# Control_board_POD_CMS.net
KiCad netlist of a schematic drawn in EAGLE
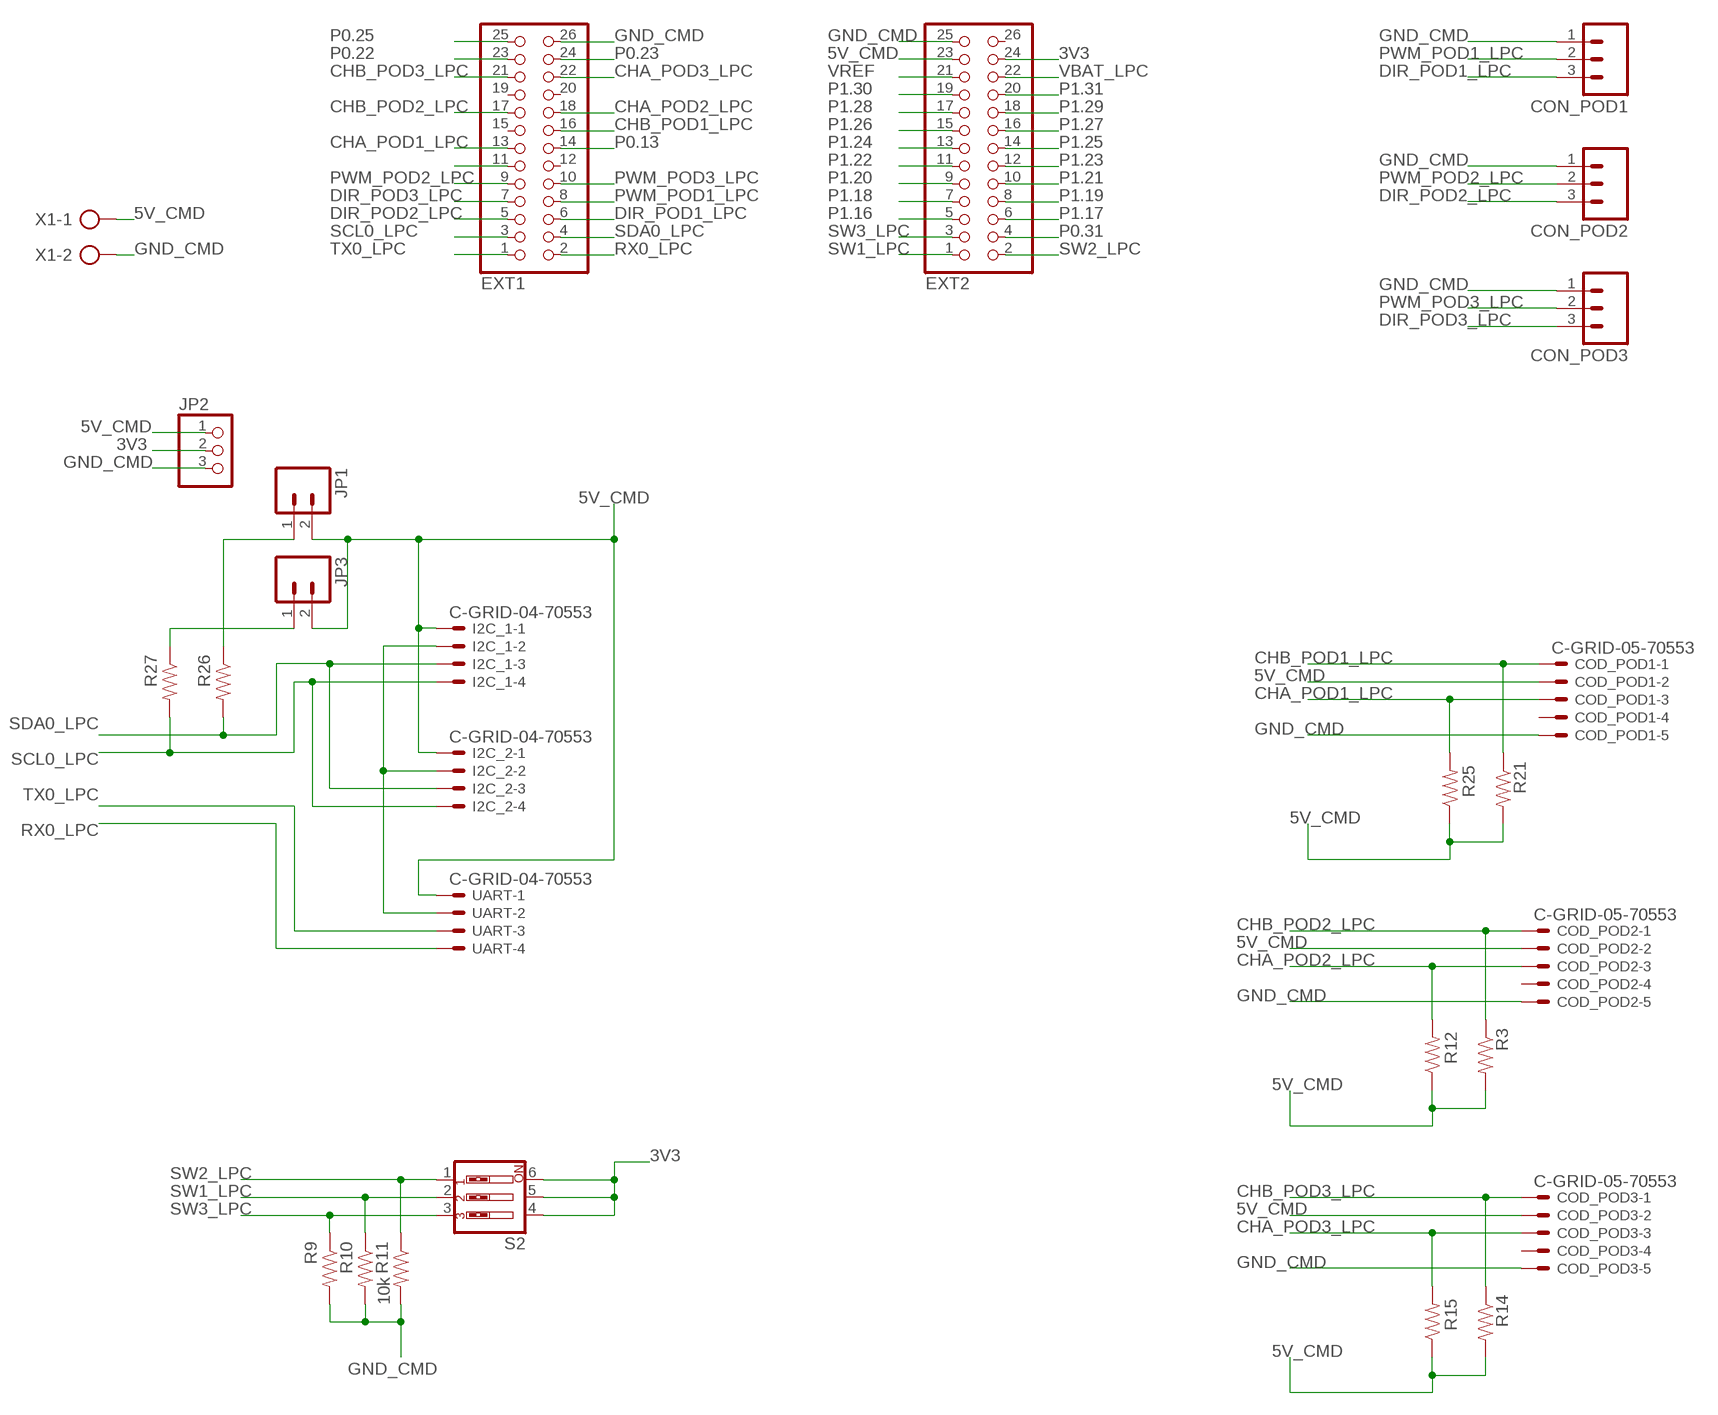
[diagram p0: schematic, sheet 1, part 1 of 2]
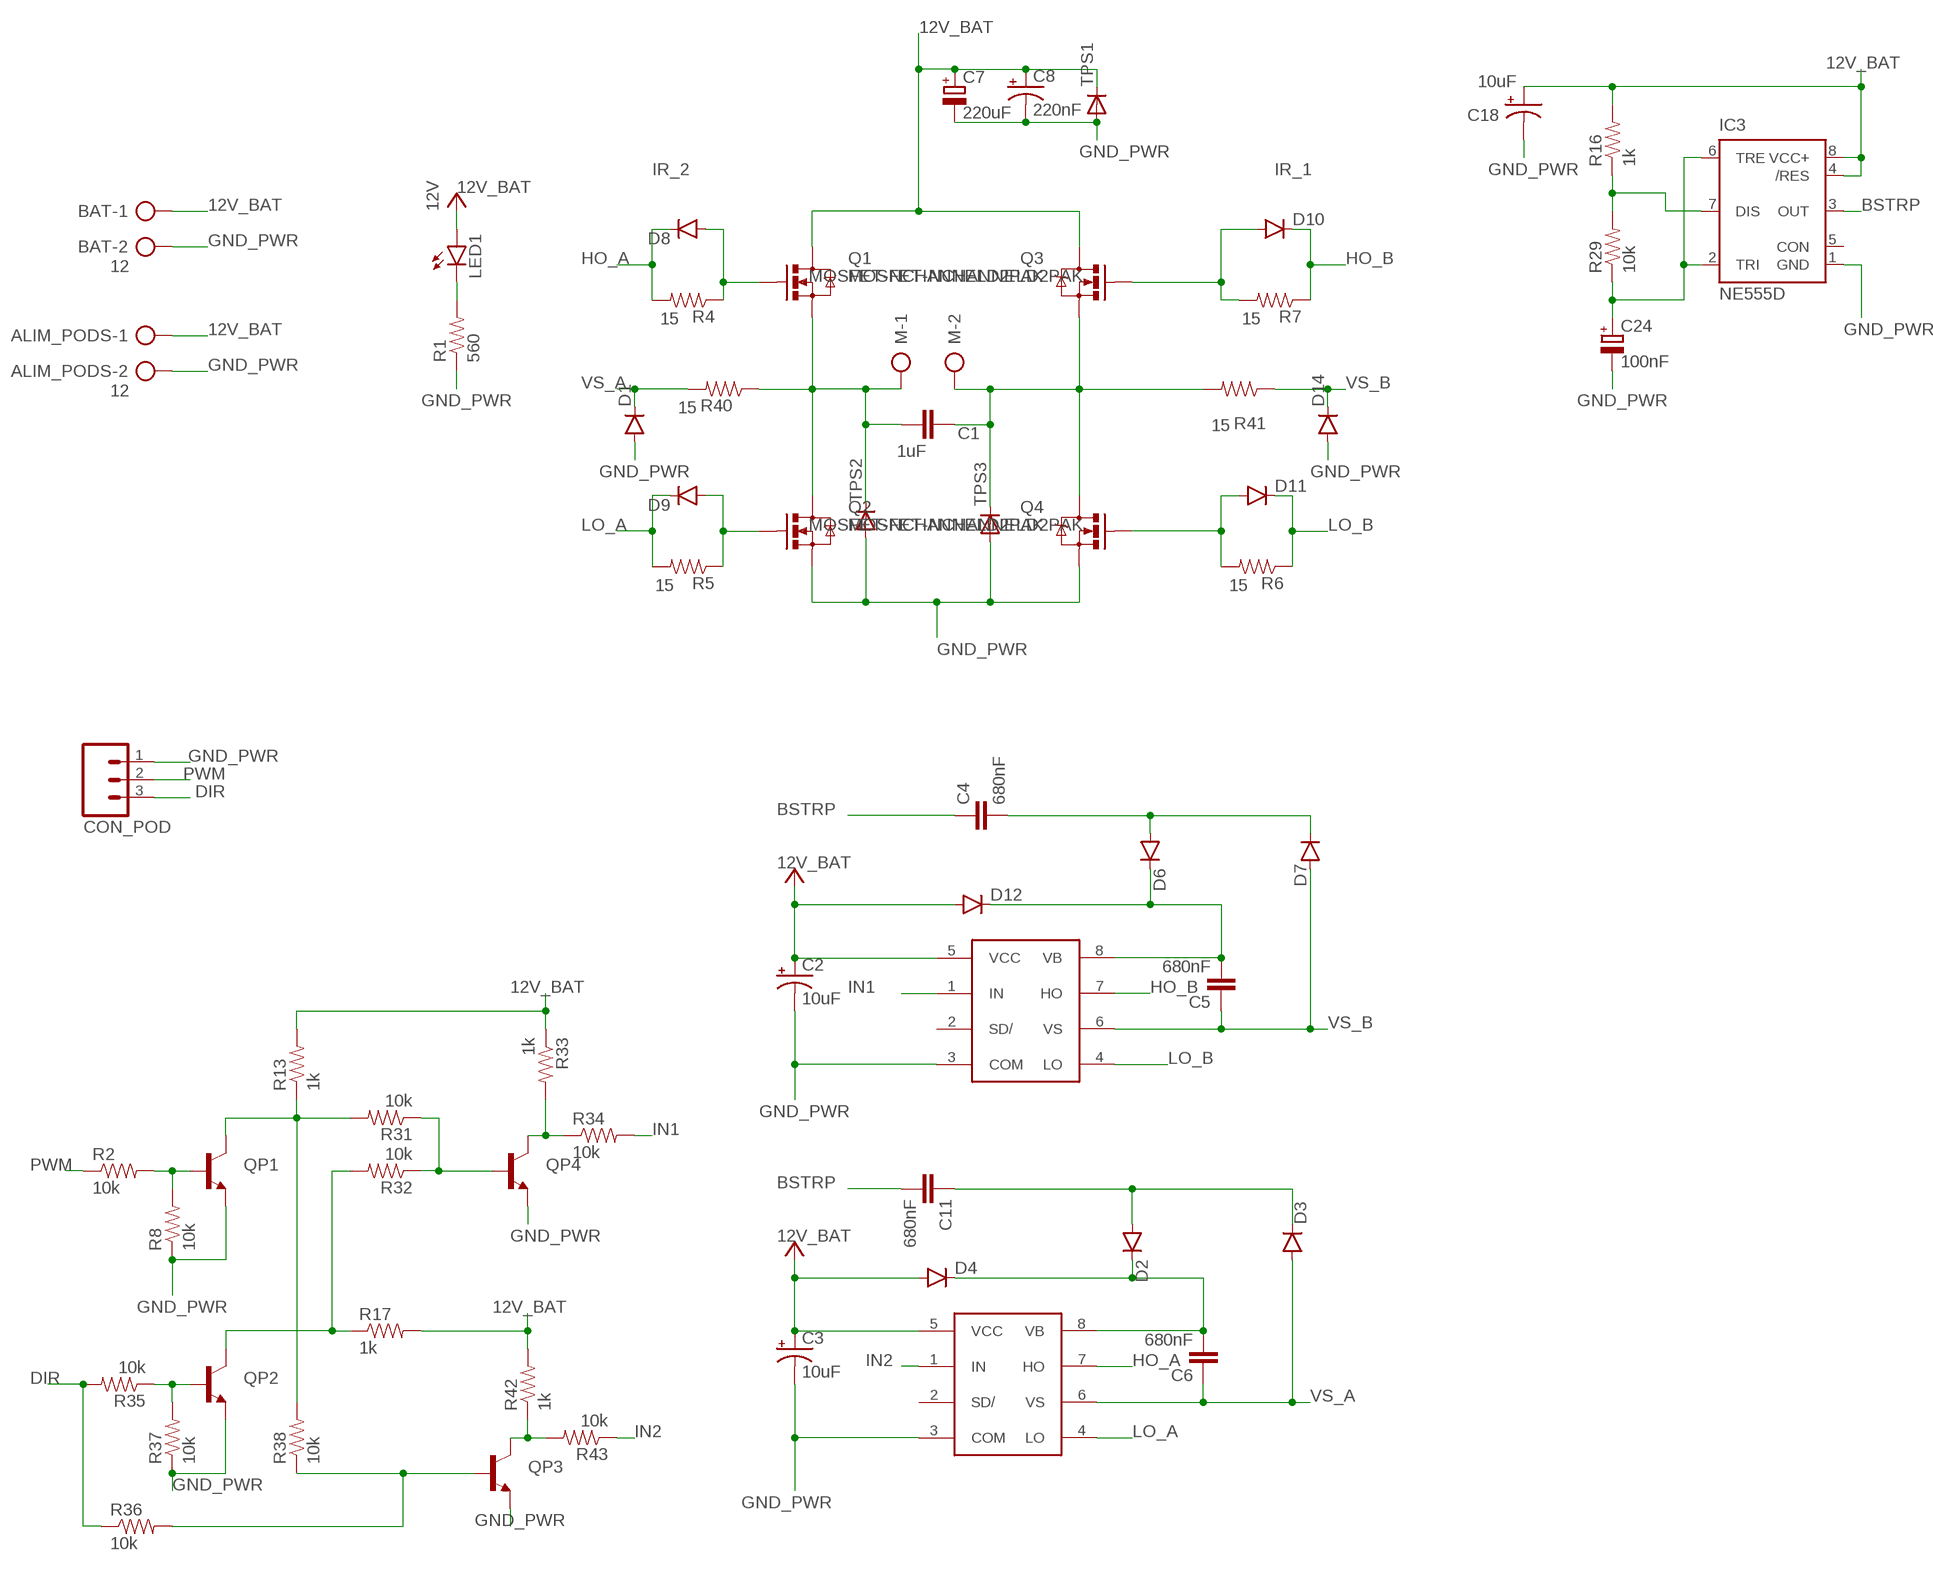
[diagram p1: schematic, sheet 1, part 2 of 2]

(export (version "E")
  (design (tool "Eeschema 10.0.6"))
  (components
    (comp (ref "ALIM_PODS")
      (value "12")
      (footprint "eagle-import:AK500_2")
      (libsource (lib "eagle-import") (part "AK500/2"))
    )
    (comp (ref "BAT")
      (value "12")
      (footprint "eagle-import:AK500_2")
      (libsource (lib "eagle-import") (part "AK500/2"))
    )
    (comp (ref "C1")
      (value "1uF")
      (footprint "eagle-import:0603-CAP")
      (libsource (lib "eagle-import") (part "CAP0603-CAP"))
    )
    (comp (ref "C2")
      (value "10uF")
      (footprint "eagle-import:EIA3216")
      (libsource (lib "eagle-import") (part "10UF-16V-10%(TANT)"))
    )
    (comp (ref "C3")
      (value "10uF")
      (footprint "eagle-import:EIA3216")
      (libsource (lib "eagle-import") (part "10UF-16V-10%(TANT)"))
    )
    (comp (ref "C4")
      (value "680nF")
      (footprint "eagle-import:0805")
      (libsource (lib "eagle-import") (part "SparkFun-Capacitors_CAP0805"))
    )
    (comp (ref "C5")
      (value "680nF")
      (footprint "eagle-import:1206")
      (libsource (lib "eagle-import") (part "SparkFun-Capacitors_CAP1206"))
    )
    (comp (ref "C6")
      (value "680nF")
      (footprint "eagle-import:1206")
      (libsource (lib "eagle-import") (part "SparkFun-Capacitors_CAP1206"))
    )
    (comp (ref "C7")
      (value "220uF")
      (footprint "eagle-import:D_7343-31R")
      (libsource (lib "eagle-import") (part "CPOL-EUD/7343-31R"))
    )
    (comp (ref "C8")
      (value "220nF")
      (footprint "eagle-import:EIA3216")
      (libsource (lib "eagle-import") (part "10UF-16V-10%(TANT)"))
    )
    (comp (ref "C11")
      (value "680nF")
      (footprint "eagle-import:0805")
      (libsource (lib "eagle-import") (part "SparkFun-Capacitors_CAP0805"))
    )
    (comp (ref "C18")
      (value "10uF")
      (footprint "eagle-import:EIA3216")
      (fields (field (name "PROD_ID") "CAP-00811"))
      (libsource (lib "eagle-import") (part "10UF-16V-10%(TANT)"))
    )
    (comp (ref "C24")
      (value "100nF")
      (footprint "eagle-import:R_2012-12R")
      (libsource (lib "eagle-import") (part "CPOL-EUR/2012-12R"))
    )
    (comp (ref "COD_POD1")
      (value "C-GRID-05-70553")
      (footprint "eagle-import:70553-05")
      (libsource (lib "eagle-import") (part "C-GRID-05-70553"))
    )
    (comp (ref "COD_POD2")
      (value "C-GRID-05-70553")
      (footprint "eagle-import:70553-05")
      (libsource (lib "eagle-import") (part "C-GRID-05-70553"))
    )
    (comp (ref "COD_POD3")
      (value "C-GRID-05-70553")
      (footprint "eagle-import:70553-05")
      (libsource (lib "eagle-import") (part "C-GRID-05-70553"))
    )
    (comp (ref "CON_POD")
      (value "M03PTH")
      (footprint "eagle-import:1X03")
      (libsource (lib "eagle-import") (part "M03PTH"))
    )
    (comp (ref "CON_POD1")
      (value "M03PTH")
      (footprint "eagle-import:1X03")
      (libsource (lib "eagle-import") (part "M03PTH"))
    )
    (comp (ref "CON_POD2")
      (value "M03PTH")
      (footprint "eagle-import:1X03")
      (libsource (lib "eagle-import") (part "M03PTH"))
    )
    (comp (ref "CON_POD3")
      (value "M03PTH")
      (footprint "eagle-import:1X03")
      (libsource (lib "eagle-import") (part "M03PTH"))
    )
    (comp (ref "D1")
      (value "DIODESOD")
      (footprint "eagle-import:SOD-323")
      (libsource (lib "eagle-import") (part "DIODESOD"))
    )
    (comp (ref "D2")
      (value "DIODESOD")
      (footprint "eagle-import:SOD-323")
      (libsource (lib "eagle-import") (part "DIODESOD"))
    )
    (comp (ref "D3")
      (value "DIODESOD")
      (footprint "eagle-import:SOD-323")
      (libsource (lib "eagle-import") (part "DIODESOD"))
    )
    (comp (ref "D4")
      (value "DIODESOD")
      (footprint "eagle-import:SOD-323")
      (libsource (lib "eagle-import") (part "DIODESOD"))
    )
    (comp (ref "D6")
      (value "DIODESOD")
      (footprint "eagle-import:SOD-323")
      (libsource (lib "eagle-import") (part "DIODESOD"))
    )
    (comp (ref "D7")
      (value "DIODESOD")
      (footprint "eagle-import:SOD-323")
      (libsource (lib "eagle-import") (part "DIODESOD"))
    )
    (comp (ref "D8")
      (value "DIODESOD")
      (footprint "eagle-import:SOD-323")
      (libsource (lib "eagle-import") (part "DIODESOD"))
    )
    (comp (ref "D9")
      (value "DIODESOD")
      (footprint "eagle-import:SOD-323")
      (libsource (lib "eagle-import") (part "DIODESOD"))
    )
    (comp (ref "D10")
      (value "DIODESOD")
      (footprint "eagle-import:SOD-323")
      (libsource (lib "eagle-import") (part "DIODESOD"))
    )
    (comp (ref "D11")
      (value "DIODESOD")
      (footprint "eagle-import:SOD-323")
      (libsource (lib "eagle-import") (part "DIODESOD"))
    )
    (comp (ref "D12")
      (value "DIODESOD")
      (footprint "eagle-import:SOD-323")
      (libsource (lib "eagle-import") (part "DIODESOD"))
    )
    (comp (ref "D14")
      (value "DIODESOD")
      (footprint "eagle-import:SOD-323")
      (libsource (lib "eagle-import") (part "DIODESOD"))
    )
    (comp (ref "EXT1")
      (value "PINHD-2X13")
      (footprint "eagle-import:2X13")
      (libsource (lib "eagle-import") (part "PINHD-2X13"))
    )
    (comp (ref "EXT2")
      (value "PINHD-2X13")
      (footprint "eagle-import:2X13")
      (libsource (lib "eagle-import") (part "PINHD-2X13"))
    )
    (comp (ref "I2C_1")
      (value "C-GRID-04-70553")
      (footprint "eagle-import:70553-04")
      (libsource (lib "eagle-import") (part "C-GRID-04-70553"))
    )
    (comp (ref "I2C_2")
      (value "C-GRID-04-70553")
      (footprint "eagle-import:70553-04")
      (libsource (lib "eagle-import") (part "C-GRID-04-70553"))
    )
    (comp (ref "IC3")
      (value "NE555D")
      (footprint "eagle-import:SO08")
      (libsource (lib "eagle-import") (part "NE555D"))
    )
    (comp (ref "IR2184SPBF1")
      (value "IR2184SPBF")
      (footprint "eagle-import:SO08")
      (libsource (lib "eagle-import") (part "IR2184SPBF"))
    )
    (comp (ref "IR2184SPBF2")
      (value "IR2184SPBF")
      (footprint "eagle-import:SO08")
      (libsource (lib "eagle-import") (part "IR2184SPBF"))
    )
    (comp (ref "JP1")
      (value "M02PTH")
      (footprint "eagle-import:1X02")
      (libsource (lib "eagle-import") (part "M02PTH"))
    )
    (comp (ref "JP2")
      (value "PINHD-1X3")
      (footprint "eagle-import:1X03")
      (libsource (lib "eagle-import") (part "PINHD-1X3"))
    )
    (comp (ref "JP3")
      (value "M02PTH")
      (footprint "eagle-import:1X02")
      (libsource (lib "eagle-import") (part "M02PTH"))
    )
    (comp (ref "LED1")
      (value "LED-WHITE")
      (footprint "eagle-import:LED-1206")
      (libsource (lib "eagle-import") (part "LED-WHITE"))
    )
    (comp (ref "M")
      (value "AK500/2")
      (footprint "eagle-import:AK500_2")
      (libsource (lib "eagle-import") (part "AK500/2"))
    )
    (comp (ref "Q1")
      (value "MOSFET-NCHANNELD2PAK")
      (footprint "eagle-import:D2PAK-3")
      (libsource (lib "eagle-import") (part "MOSFET-NCHANNELD2PAK"))
    )
    (comp (ref "Q2")
      (value "MOSFET-NCHANNELD2PAK")
      (footprint "eagle-import:D2PAK-3")
      (libsource (lib "eagle-import") (part "MOSFET-NCHANNELD2PAK"))
    )
    (comp (ref "Q3")
      (value "MOSFET-NCHANNELD2PAK")
      (footprint "eagle-import:D2PAK-3")
      (libsource (lib "eagle-import") (part "MOSFET-NCHANNELD2PAK"))
    )
    (comp (ref "Q4")
      (value "MOSFET-NCHANNELD2PAK")
      (footprint "eagle-import:D2PAK-3")
      (libsource (lib "eagle-import") (part "MOSFET-NCHANNELD2PAK"))
    )
    (comp (ref "QP1")
      (value "TRANSISTOR_NPNSOT23-3")
      (footprint "eagle-import:SOT23-3")
      (libsource (lib "eagle-import") (part "TRANSISTOR_NPNSOT23-3"))
    )
    (comp (ref "QP2")
      (value "TRANSISTOR_NPNSOT23-3")
      (footprint "eagle-import:SOT23-3")
      (libsource (lib "eagle-import") (part "TRANSISTOR_NPNSOT23-3"))
    )
    (comp (ref "QP3")
      (value "TRANSISTOR_NPNSOT23-3")
      (footprint "eagle-import:SOT23-3")
      (libsource (lib "eagle-import") (part "TRANSISTOR_NPNSOT23-3"))
    )
    (comp (ref "QP4")
      (value "TRANSISTOR_NPNSOT23-3")
      (footprint "eagle-import:SOT23-3")
      (libsource (lib "eagle-import") (part "TRANSISTOR_NPNSOT23-3"))
    )
    (comp (ref "R1")
      (value "560")
      (footprint "eagle-import:1206")
      (libsource (lib "eagle-import") (part "RESISTOR1206"))
    )
    (comp (ref "R2")
      (value "10k")
      (footprint "eagle-import:0603-RES")
      (libsource (lib "eagle-import") (part "SparkFun-Passives_RESISTOR0603-RES"))
    )
    (comp (ref "R3")
      (value "3k3")
      (footprint "eagle-import:0603-RES")
      (libsource (lib "eagle-import") (part "SparkFun-Passives_RESISTOR0603-RES"))
    )
    (comp (ref "R4")
      (value "15")
      (footprint "eagle-import:0805")
      (libsource (lib "eagle-import") (part "SparkFun-Passives_RESISTOR0805-RES"))
    )
    (comp (ref "R5")
      (value "15")
      (footprint "eagle-import:0805")
      (libsource (lib "eagle-import") (part "SparkFun-Passives_RESISTOR0805-RES"))
    )
    (comp (ref "R6")
      (value "15")
      (footprint "eagle-import:0805")
      (libsource (lib "eagle-import") (part "SparkFun-Passives_RESISTOR0805-RES"))
    )
    (comp (ref "R7")
      (value "15")
      (footprint "eagle-import:0805")
      (libsource (lib "eagle-import") (part "SparkFun-Passives_RESISTOR0805-RES"))
    )
    (comp (ref "R8")
      (value "10k")
      (footprint "eagle-import:0603-RES")
      (libsource (lib "eagle-import") (part "SparkFun-Passives_RESISTOR0603-RES"))
    )
    (comp (ref "R9")
      (value "10k")
      (footprint "eagle-import:0603-RES")
      (libsource (lib "eagle-import") (part "SparkFun-Passives_RESISTOR0603-RES"))
    )
    (comp (ref "R10")
      (value "10k")
      (footprint "eagle-import:0603-RES")
      (libsource (lib "eagle-import") (part "SparkFun-Passives_RESISTOR0603-RES"))
    )
    (comp (ref "R11")
      (value "10k")
      (footprint "eagle-import:0603-RES")
      (libsource (lib "eagle-import") (part "SparkFun-Passives_RESISTOR0603-RES"))
    )
    (comp (ref "R12")
      (value "3k3")
      (footprint "eagle-import:0603-RES")
      (libsource (lib "eagle-import") (part "SparkFun-Passives_RESISTOR0603-RES"))
    )
    (comp (ref "R13")
      (value "1k")
      (footprint "eagle-import:0603-RES")
      (libsource (lib "eagle-import") (part "SparkFun-Passives_RESISTOR0603-RES"))
    )
    (comp (ref "R14")
      (value "3k3")
      (footprint "eagle-import:0603-RES")
      (libsource (lib "eagle-import") (part "SparkFun-Passives_RESISTOR0603-RES"))
    )
    (comp (ref "R15")
      (value "3k3")
      (footprint "eagle-import:0603-RES")
      (libsource (lib "eagle-import") (part "SparkFun-Passives_RESISTOR0603-RES"))
    )
    (comp (ref "R16")
      (value "1k")
      (footprint "eagle-import:0603-RES")
      (libsource (lib "eagle-import") (part "SparkFun-Passives_RESISTOR0603-RES"))
    )
    (comp (ref "R17")
      (value "1k")
      (footprint "eagle-import:0603-RES")
      (libsource (lib "eagle-import") (part "SparkFun-Passives_RESISTOR0603-RES"))
    )
    (comp (ref "R21")
      (value "3k3")
      (footprint "eagle-import:0603-RES")
      (libsource (lib "eagle-import") (part "SparkFun-Passives_RESISTOR0603-RES"))
    )
    (comp (ref "R25")
      (value "3k3")
      (footprint "eagle-import:0603-RES")
      (libsource (lib "eagle-import") (part "SparkFun-Passives_RESISTOR0603-RES"))
    )
    (comp (ref "R26")
      (value "3.3k")
      (footprint "eagle-import:0603-RES")
      (libsource (lib "eagle-import") (part "SparkFun-Passives_RESISTOR0603-RES"))
    )
    (comp (ref "R27")
      (value "3.3k")
      (footprint "eagle-import:0603-RES")
      (libsource (lib "eagle-import") (part "SparkFun-Passives_RESISTOR0603-RES"))
    )
    (comp (ref "R29")
      (value "10k")
      (footprint "eagle-import:0603-RES")
      (libsource (lib "eagle-import") (part "SparkFun-Passives_RESISTOR0603-RES"))
    )
    (comp (ref "R31")
      (value "10k")
      (footprint "eagle-import:0603-RES")
      (libsource (lib "eagle-import") (part "SparkFun-Passives_RESISTOR0603-RES"))
    )
    (comp (ref "R32")
      (value "10k")
      (footprint "eagle-import:0603-RES")
      (libsource (lib "eagle-import") (part "SparkFun-Passives_RESISTOR0603-RES"))
    )
    (comp (ref "R33")
      (value "1k")
      (footprint "eagle-import:0603-RES")
      (libsource (lib "eagle-import") (part "SparkFun-Passives_RESISTOR0603-RES"))
    )
    (comp (ref "R34")
      (value "10k")
      (footprint "eagle-import:0603-RES")
      (libsource (lib "eagle-import") (part "SparkFun-Passives_RESISTOR0603-RES"))
    )
    (comp (ref "R35")
      (value "10k")
      (footprint "eagle-import:0603-RES")
      (libsource (lib "eagle-import") (part "SparkFun-Passives_RESISTOR0603-RES"))
    )
    (comp (ref "R36")
      (value "10k")
      (footprint "eagle-import:0603-RES")
      (libsource (lib "eagle-import") (part "SparkFun-Passives_RESISTOR0603-RES"))
    )
    (comp (ref "R37")
      (value "10k")
      (footprint "eagle-import:0603-RES")
      (libsource (lib "eagle-import") (part "SparkFun-Passives_RESISTOR0603-RES"))
    )
    (comp (ref "R38")
      (value "10k")
      (footprint "eagle-import:0603-RES")
      (libsource (lib "eagle-import") (part "SparkFun-Passives_RESISTOR0603-RES"))
    )
    (comp (ref "R40")
      (value "15")
      (footprint "eagle-import:0603-RES")
      (libsource (lib "eagle-import") (part "SparkFun-Passives_RESISTOR0603-RES"))
    )
    (comp (ref "R41")
      (value "15")
      (footprint "eagle-import:0603-RES")
      (libsource (lib "eagle-import") (part "SparkFun-Passives_RESISTOR0603-RES"))
    )
    (comp (ref "R42")
      (value "1k")
      (footprint "eagle-import:0603-RES")
      (libsource (lib "eagle-import") (part "SparkFun-Passives_RESISTOR0603-RES"))
    )
    (comp (ref "R43")
      (value "10k")
      (footprint "eagle-import:0603-RES")
      (libsource (lib "eagle-import") (part "SparkFun-Passives_RESISTOR0603-RES"))
    )
    (comp (ref "S2")
      (value "SW_DIP-3")
      (footprint "eagle-import:EDG-03")
      (libsource (lib "eagle-import") (part "SW_DIP-3"))
    )
    (comp (ref "TPS1")
      (value "DIODE-SMC")
      (footprint "eagle-import:SMC")
      (libsource (lib "eagle-import") (part "DIODE-SMC"))
    )
    (comp (ref "TPS2")
      (value "DIODE-SMC")
      (footprint "eagle-import:SMC")
      (libsource (lib "eagle-import") (part "DIODE-SMC"))
    )
    (comp (ref "TPS3")
      (value "DIODE-SMC")
      (footprint "eagle-import:SMC")
      (libsource (lib "eagle-import") (part "DIODE-SMC"))
    )
    (comp (ref "UART")
      (value "C-GRID-04-70553")
      (footprint "eagle-import:70553-04")
      (libsource (lib "eagle-import") (part "C-GRID-04-70553"))
    )
    (comp (ref "X1")
      (value "AK500/2")
      (footprint "eagle-import:AK500_2")
      (libsource (lib "eagle-import") (part "AK500/2"))
    )
  )
  (nets
    (net (code "1") (name "/3V3") (class "Default")
      (node (ref "EXT2") (pin "24") (pinfunction "24_24") (pintype "passive"))
      (node (ref "JP2") (pin "2") (pinfunction "2_2") (pintype "passive"))
      (node (ref "S2") (pin "4") (pinfunction "4_4") (pintype "passive"))
      (node (ref "S2") (pin "5") (pinfunction "5_5") (pintype "passive"))
      (node (ref "S2") (pin "6") (pinfunction "6_6") (pintype "passive"))
    )
    (net (code "2") (name "/5V_CMD") (class "Default")
      (node (ref "COD_POD1") (pin "2") (pinfunction "S_2") (pintype "passive"))
      (node (ref "COD_POD2") (pin "2") (pinfunction "S_2") (pintype "passive"))
      (node (ref "COD_POD3") (pin "2") (pinfunction "S_2") (pintype "passive"))
      (node (ref "EXT2") (pin "23") (pinfunction "23_23") (pintype "passive"))
      (node (ref "I2C_1") (pin "1") (pinfunction "S_1") (pintype "passive"))
      (node (ref "I2C_2") (pin "1") (pinfunction "S_1") (pintype "passive"))
      (node (ref "JP1") (pin "2") (pinfunction "2_2") (pintype "passive"))
      (node (ref "JP2") (pin "1") (pinfunction "1_1") (pintype "passive"))
      (node (ref "JP3") (pin "2") (pinfunction "2_2") (pintype "passive"))
      (node (ref "R12") (pin "1") (pinfunction "1_1") (pintype "passive"))
      (node (ref "R14") (pin "2") (pinfunction "2_2") (pintype "passive"))
      (node (ref "R15") (pin "1") (pinfunction "1_1") (pintype "passive"))
      (node (ref "R21") (pin "2") (pinfunction "2_2") (pintype "passive"))
      (node (ref "R25") (pin "1") (pinfunction "1_1") (pintype "passive"))
      (node (ref "R3") (pin "2") (pinfunction "2_2") (pintype "passive"))
      (node (ref "UART") (pin "1") (pinfunction "S_1") (pintype "passive"))
      (node (ref "X1") (pin "1") (pinfunction "KL_1") (pintype "passive"))
    )
    (net (code "3") (name "/BSTRP") (class "Default")
      (node (ref "C11") (pin "2") (pinfunction "2_2") (pintype "passive"))
      (node (ref "C4") (pin "1") (pinfunction "1_1") (pintype "passive"))
      (node (ref "IC3") (pin "3") (pinfunction "OUT_3") (pintype "output"))
    )
    (net (code "4") (name "/CHA_POD1_LPC") (class "Default")
      (node (ref "COD_POD1") (pin "3") (pinfunction "S_3") (pintype "passive"))
      (node (ref "EXT1") (pin "13") (pinfunction "13_13") (pintype "passive"))
      (node (ref "R25") (pin "2") (pinfunction "2_2") (pintype "passive"))
    )
    (net (code "5") (name "/CHA_POD2_LPC") (class "Default")
      (node (ref "COD_POD2") (pin "3") (pinfunction "S_3") (pintype "passive"))
      (node (ref "EXT1") (pin "18") (pinfunction "18_18") (pintype "passive"))
      (node (ref "R12") (pin "2") (pinfunction "2_2") (pintype "passive"))
    )
    (net (code "6") (name "/CHA_POD3_LPC") (class "Default")
      (node (ref "COD_POD3") (pin "3") (pinfunction "S_3") (pintype "passive"))
      (node (ref "EXT1") (pin "22") (pinfunction "22_22") (pintype "passive"))
      (node (ref "R15") (pin "2") (pinfunction "2_2") (pintype "passive"))
    )
    (net (code "7") (name "/CHB_POD1_LPC") (class "Default")
      (node (ref "COD_POD1") (pin "1") (pinfunction "S_1") (pintype "passive"))
      (node (ref "EXT1") (pin "16") (pinfunction "16_16") (pintype "passive"))
      (node (ref "R21") (pin "1") (pinfunction "1_1") (pintype "passive"))
    )
    (net (code "8") (name "/CHB_POD2_LPC") (class "Default")
      (node (ref "COD_POD2") (pin "1") (pinfunction "S_1") (pintype "passive"))
      (node (ref "EXT1") (pin "17") (pinfunction "17_17") (pintype "passive"))
      (node (ref "R3") (pin "1") (pinfunction "1_1") (pintype "passive"))
    )
    (net (code "9") (name "/CHB_POD3_LPC") (class "Default")
      (node (ref "COD_POD3") (pin "1") (pinfunction "S_1") (pintype "passive"))
      (node (ref "EXT1") (pin "21") (pinfunction "21_21") (pintype "passive"))
      (node (ref "R14") (pin "1") (pinfunction "1_1") (pintype "passive"))
    )
    (net (code "10") (name "/DIR") (class "Default")
      (node (ref "CON_POD") (pin "3") (pinfunction "3_3") (pintype "passive"))
      (node (ref "R35") (pin "2") (pinfunction "2_2") (pintype "passive"))
      (node (ref "R36") (pin "1") (pinfunction "1_1") (pintype "passive"))
    )
    (net (code "11") (name "/DIR_POD1_LPC") (class "Default")
      (node (ref "CON_POD1") (pin "3") (pinfunction "3_3") (pintype "passive"))
      (node (ref "EXT1") (pin "6") (pinfunction "6_6") (pintype "passive"))
    )
    (net (code "12") (name "/DIR_POD2_LPC") (class "Default")
      (node (ref "CON_POD2") (pin "3") (pinfunction "3_3") (pintype "passive"))
      (node (ref "EXT1") (pin "5") (pinfunction "5_5") (pintype "passive"))
    )
    (net (code "13") (name "/DIR_POD3_LPC") (class "Default")
      (node (ref "CON_POD3") (pin "3") (pinfunction "3_3") (pintype "passive"))
      (node (ref "EXT1") (pin "7") (pinfunction "7_7") (pintype "passive"))
    )
    (net (code "14") (name "/GND_CMD") (class "Default")
      (node (ref "COD_POD1") (pin "5") (pinfunction "S_5") (pintype "passive"))
      (node (ref "COD_POD2") (pin "5") (pinfunction "S_5") (pintype "passive"))
      (node (ref "COD_POD3") (pin "5") (pinfunction "S_5") (pintype "passive"))
      (node (ref "CON_POD1") (pin "1") (pinfunction "1_1") (pintype "passive"))
      (node (ref "CON_POD2") (pin "1") (pinfunction "1_1") (pintype "passive"))
      (node (ref "CON_POD3") (pin "1") (pinfunction "1_1") (pintype "passive"))
      (node (ref "EXT1") (pin "26") (pinfunction "26_26") (pintype "passive"))
      (node (ref "EXT2") (pin "25") (pinfunction "25_25") (pintype "passive"))
      (node (ref "I2C_1") (pin "2") (pinfunction "S_2") (pintype "passive"))
      (node (ref "I2C_2") (pin "2") (pinfunction "S_2") (pintype "passive"))
      (node (ref "JP2") (pin "3") (pinfunction "3_3") (pintype "passive"))
      (node (ref "R10") (pin "2") (pinfunction "2_2") (pintype "passive"))
      (node (ref "R11") (pin "2") (pinfunction "2_2") (pintype "passive"))
      (node (ref "R9") (pin "2") (pinfunction "2_2") (pintype "passive"))
      (node (ref "UART") (pin "2") (pinfunction "S_2") (pintype "passive"))
      (node (ref "X1") (pin "2") (pinfunction "KL_2") (pintype "passive"))
    )
    (net (code "15") (name "/GND_PWR") (class "Default")
      (node (ref "ALIM_PODS") (pin "2") (pinfunction "KL_2") (pintype "passive"))
      (node (ref "BAT") (pin "2") (pinfunction "KL_2") (pintype "passive"))
      (node (ref "C18") (pin "C") (pinfunction "-_C") (pintype "passive"))
      (node (ref "C2") (pin "C") (pinfunction "-_C") (pintype "passive"))
      (node (ref "C24") (pin "-") (pinfunction "-_-") (pintype "passive"))
      (node (ref "C3") (pin "C") (pinfunction "-_C") (pintype "passive"))
      (node (ref "C7") (pin "-") (pinfunction "-_-") (pintype "passive"))
      (node (ref "C8") (pin "C") (pinfunction "-_C") (pintype "passive"))
      (node (ref "CON_POD") (pin "1") (pinfunction "1_1") (pintype "passive"))
      (node (ref "D1") (pin "A") (pinfunction "A_A") (pintype "passive"))
      (node (ref "D14") (pin "A") (pinfunction "A_A") (pintype "passive"))
      (node (ref "IC3") (pin "1") (pinfunction "GND_1") (pintype "power_in"))
      (node (ref "IR2184SPBF1") (pin "3") (pinfunction "COM_3") (pintype "bidirectional"))
      (node (ref "IR2184SPBF2") (pin "3") (pinfunction "COM_3") (pintype "bidirectional"))
      (node (ref "Q2") (pin "3") (pinfunction "S_3") (pintype "passive"))
      (node (ref "Q4") (pin "3") (pinfunction "S_3") (pintype "passive"))
      (node (ref "QP1") (pin "2") (pinfunction "E_2") (pintype "passive"))
      (node (ref "QP2") (pin "2") (pinfunction "E_2") (pintype "passive"))
      (node (ref "QP3") (pin "2") (pinfunction "E_2") (pintype "passive"))
      (node (ref "QP4") (pin "2") (pinfunction "E_2") (pintype "passive"))
      (node (ref "R1") (pin "1") (pinfunction "1_1") (pintype "passive"))
      (node (ref "R37") (pin "1") (pinfunction "1_1") (pintype "passive"))
      (node (ref "R8") (pin "1") (pinfunction "1_1") (pintype "passive"))
      (node (ref "TPS1") (pin "A") (pinfunction "A_A") (pintype "passive"))
      (node (ref "TPS2") (pin "A") (pinfunction "A_A") (pintype "passive"))
      (node (ref "TPS3") (pin "A") (pinfunction "A_A") (pintype "passive"))
    )
    (net (code "16") (name "/HO_A") (class "Default")
      (node (ref "D8") (pin "C") (pinfunction "C_C") (pintype "passive"))
      (node (ref "IR2184SPBF2") (pin "7") (pinfunction "HO_7") (pintype "bidirectional"))
      (node (ref "R4") (pin "2") (pinfunction "2_2") (pintype "passive"))
    )
    (net (code "17") (name "/HO_B") (class "Default")
      (node (ref "D10") (pin "C") (pinfunction "C_C") (pintype "passive"))
      (node (ref "IR2184SPBF1") (pin "7") (pinfunction "HO_7") (pintype "bidirectional"))
      (node (ref "R7") (pin "1") (pinfunction "1_1") (pintype "passive"))
    )
    (net (code "18") (name "/IN1") (class "Default")
      (node (ref "IR2184SPBF1") (pin "1") (pinfunction "IN_1") (pintype "bidirectional"))
      (node (ref "R34") (pin "2") (pinfunction "2_2") (pintype "passive"))
    )
    (net (code "19") (name "/IN2") (class "Default")
      (node (ref "IR2184SPBF2") (pin "1") (pinfunction "IN_1") (pintype "bidirectional"))
      (node (ref "R43") (pin "1") (pinfunction "1_1") (pintype "passive"))
    )
    (net (code "20") (name "/LO_A") (class "Default")
      (node (ref "D9") (pin "C") (pinfunction "C_C") (pintype "passive"))
      (node (ref "IR2184SPBF2") (pin "4") (pinfunction "LO_4") (pintype "bidirectional"))
      (node (ref "R5") (pin "2") (pinfunction "2_2") (pintype "passive"))
    )
    (net (code "21") (name "/LO_B") (class "Default")
      (node (ref "D11") (pin "C") (pinfunction "C_C") (pintype "passive"))
      (node (ref "IR2184SPBF1") (pin "4") (pinfunction "LO_4") (pintype "bidirectional"))
      (node (ref "R6") (pin "1") (pinfunction "1_1") (pintype "passive"))
    )
    (net (code "22") (name "/P0.13") (class "Default")
      (node (ref "EXT1") (pin "14") (pinfunction "14_14") (pintype "passive"))
    )
    (net (code "23") (name "/P0.22") (class "Default")
      (node (ref "EXT1") (pin "23") (pinfunction "23_23") (pintype "passive"))
    )
    (net (code "24") (name "/P0.23") (class "Default")
      (node (ref "EXT1") (pin "24") (pinfunction "24_24") (pintype "passive"))
    )
    (net (code "25") (name "/P0.25") (class "Default")
      (node (ref "EXT1") (pin "25") (pinfunction "25_25") (pintype "passive"))
    )
    (net (code "26") (name "/P0.31") (class "Default")
      (node (ref "EXT2") (pin "4") (pinfunction "4_4") (pintype "passive"))
    )
    (net (code "27") (name "/P1.16") (class "Default")
      (node (ref "EXT2") (pin "5") (pinfunction "5_5") (pintype "passive"))
    )
    (net (code "28") (name "/P1.17") (class "Default")
      (node (ref "EXT2") (pin "6") (pinfunction "6_6") (pintype "passive"))
    )
    (net (code "29") (name "/P1.18") (class "Default")
      (node (ref "EXT2") (pin "7") (pinfunction "7_7") (pintype "passive"))
    )
    (net (code "30") (name "/P1.19") (class "Default")
      (node (ref "EXT2") (pin "8") (pinfunction "8_8") (pintype "passive"))
    )
    (net (code "31") (name "/P1.20") (class "Default")
      (node (ref "EXT2") (pin "9") (pinfunction "9_9") (pintype "passive"))
    )
    (net (code "32") (name "/P1.21") (class "Default")
      (node (ref "EXT2") (pin "10") (pinfunction "10_10") (pintype "passive"))
    )
    (net (code "33") (name "/P1.22") (class "Default")
      (node (ref "EXT2") (pin "11") (pinfunction "11_11") (pintype "passive"))
    )
    (net (code "34") (name "/P1.23") (class "Default")
      (node (ref "EXT2") (pin "12") (pinfunction "12_12") (pintype "passive"))
    )
    (net (code "35") (name "/P1.24") (class "Default")
      (node (ref "EXT2") (pin "13") (pinfunction "13_13") (pintype "passive"))
    )
    (net (code "36") (name "/P1.25") (class "Default")
      (node (ref "EXT2") (pin "14") (pinfunction "14_14") (pintype "passive"))
    )
    (net (code "37") (name "/P1.26") (class "Default")
      (node (ref "EXT2") (pin "15") (pinfunction "15_15") (pintype "passive"))
    )
    (net (code "38") (name "/P1.27") (class "Default")
      (node (ref "EXT2") (pin "16") (pinfunction "16_16") (pintype "passive"))
    )
    (net (code "39") (name "/P1.28") (class "Default")
      (node (ref "EXT2") (pin "17") (pinfunction "17_17") (pintype "passive"))
    )
    (net (code "40") (name "/P1.29") (class "Default")
      (node (ref "EXT2") (pin "18") (pinfunction "18_18") (pintype "passive"))
    )
    (net (code "41") (name "/P1.30") (class "Default")
      (node (ref "EXT2") (pin "19") (pinfunction "19_19") (pintype "passive"))
    )
    (net (code "42") (name "/P1.31") (class "Default")
      (node (ref "EXT2") (pin "20") (pinfunction "20_20") (pintype "passive"))
    )
    (net (code "43") (name "/PWM") (class "Default")
      (node (ref "CON_POD") (pin "2") (pinfunction "2_2") (pintype "passive"))
      (node (ref "R2") (pin "1") (pinfunction "1_1") (pintype "passive"))
    )
    (net (code "44") (name "/PWM_POD1_LPC") (class "Default")
      (node (ref "CON_POD1") (pin "2") (pinfunction "2_2") (pintype "passive"))
      (node (ref "EXT1") (pin "8") (pinfunction "8_8") (pintype "passive"))
    )
    (net (code "45") (name "/PWM_POD2_LPC") (class "Default")
      (node (ref "CON_POD2") (pin "2") (pinfunction "2_2") (pintype "passive"))
      (node (ref "EXT1") (pin "9") (pinfunction "9_9") (pintype "passive"))
    )
    (net (code "46") (name "/PWM_POD3_LPC") (class "Default")
      (node (ref "CON_POD3") (pin "2") (pinfunction "2_2") (pintype "passive"))
      (node (ref "EXT1") (pin "10") (pinfunction "10_10") (pintype "passive"))
    )
    (net (code "47") (name "/RX0_LPC") (class "Default")
      (node (ref "EXT1") (pin "2") (pinfunction "2_2") (pintype "passive"))
      (node (ref "UART") (pin "4") (pinfunction "S_4") (pintype "passive"))
    )
    (net (code "48") (name "/SCL0_LPC") (class "Default")
      (node (ref "EXT1") (pin "3") (pinfunction "3_3") (pintype "passive"))
      (node (ref "I2C_1") (pin "4") (pinfunction "S_4") (pintype "passive"))
      (node (ref "I2C_2") (pin "4") (pinfunction "S_4") (pintype "passive"))
      (node (ref "R27") (pin "2") (pinfunction "2_2") (pintype "passive"))
    )
    (net (code "49") (name "/SDA0_LPC") (class "Default")
      (node (ref "EXT1") (pin "4") (pinfunction "4_4") (pintype "passive"))
      (node (ref "I2C_1") (pin "3") (pinfunction "S_3") (pintype "passive"))
      (node (ref "I2C_2") (pin "3") (pinfunction "S_3") (pintype "passive"))
      (node (ref "R26") (pin "2") (pinfunction "2_2") (pintype "passive"))
    )
    (net (code "50") (name "/SW1_LPC") (class "Default")
      (node (ref "EXT2") (pin "1") (pinfunction "1_1") (pintype "passive"))
      (node (ref "R10") (pin "1") (pinfunction "1_1") (pintype "passive"))
      (node (ref "S2") (pin "2") (pinfunction "2_2") (pintype "passive"))
    )
    (net (code "51") (name "/SW2_LPC") (class "Default")
      (node (ref "EXT2") (pin "2") (pinfunction "2_2") (pintype "passive"))
      (node (ref "R11") (pin "1") (pinfunction "1_1") (pintype "passive"))
      (node (ref "S2") (pin "1") (pinfunction "1_1") (pintype "passive"))
    )
    (net (code "52") (name "/SW3_LPC") (class "Default")
      (node (ref "EXT2") (pin "3") (pinfunction "3_3") (pintype "passive"))
      (node (ref "R9") (pin "1") (pinfunction "1_1") (pintype "passive"))
      (node (ref "S2") (pin "3") (pinfunction "3_3") (pintype "passive"))
    )
    (net (code "53") (name "/TX0_LPC") (class "Default")
      (node (ref "EXT1") (pin "1") (pinfunction "1_1") (pintype "passive"))
      (node (ref "UART") (pin "3") (pinfunction "S_3") (pintype "passive"))
    )
    (net (code "54") (name "/VBAT_LPC") (class "Default")
      (node (ref "EXT2") (pin "22") (pinfunction "22_22") (pintype "passive"))
    )
    (net (code "55") (name "/VREF") (class "Default")
      (node (ref "EXT2") (pin "21") (pinfunction "21_21") (pintype "passive"))
    )
    (net (code "56") (name "/VS_A") (class "Default")
      (node (ref "C6") (pin "1") (pinfunction "1_1") (pintype "passive"))
      (node (ref "D1") (pin "C") (pinfunction "C_C") (pintype "passive"))
      (node (ref "D3") (pin "A") (pinfunction "A_A") (pintype "passive"))
      (node (ref "IR2184SPBF2") (pin "6") (pinfunction "VS_6") (pintype "bidirectional"))
      (node (ref "R40") (pin "2") (pinfunction "2_2") (pintype "passive"))
    )
    (net (code "57") (name "/VS_B") (class "Default")
      (node (ref "C5") (pin "1") (pinfunction "1_1") (pintype "passive"))
      (node (ref "D14") (pin "C") (pinfunction "C_C") (pintype "passive"))
      (node (ref "D7") (pin "A") (pinfunction "A_A") (pintype "passive"))
      (node (ref "IR2184SPBF1") (pin "6") (pinfunction "VS_6") (pintype "bidirectional"))
      (node (ref "R41") (pin "1") (pinfunction "1_1") (pintype "passive"))
    )
    (net (code "58") (name "12V") (class "Default")
      (node (ref "ALIM_PODS") (pin "1") (pinfunction "KL_1") (pintype "passive"))
      (node (ref "BAT") (pin "1") (pinfunction "KL_1") (pintype "passive"))
      (node (ref "C18") (pin "A") (pinfunction "+_A") (pintype "passive"))
      (node (ref "C2") (pin "A") (pinfunction "+_A") (pintype "passive"))
      (node (ref "C3") (pin "A") (pinfunction "+_A") (pintype "passive"))
      (node (ref "C7") (pin "+") (pinfunction "+_+") (pintype "passive"))
      (node (ref "C8") (pin "A") (pinfunction "+_A") (pintype "passive"))
      (node (ref "D12") (pin "A") (pinfunction "A_A") (pintype "passive"))
      (node (ref "D4") (pin "A") (pinfunction "A_A") (pintype "passive"))
      (node (ref "IC3") (pin "4") (pinfunction "/RES_4") (pintype "input"))
      (node (ref "IC3") (pin "8") (pinfunction "VCC+_8") (pintype "power_in"))
      (node (ref "IR2184SPBF1") (pin "5") (pinfunction "VCC_5") (pintype "bidirectional"))
      (node (ref "IR2184SPBF2") (pin "5") (pinfunction "VCC_5") (pintype "bidirectional"))
      (node (ref "LED1") (pin "A") (pinfunction "A_A") (pintype "passive"))
      (node (ref "Q1") (pin "4") (pinfunction "D_4") (pintype "passive"))
      (node (ref "Q3") (pin "4") (pinfunction "D_4") (pintype "passive"))
      (node (ref "R13") (pin "2") (pinfunction "2_2") (pintype "passive"))
      (node (ref "R16") (pin "2") (pinfunction "2_2") (pintype "passive"))
      (node (ref "R17") (pin "2") (pinfunction "2_2") (pintype "passive"))
      (node (ref "R33") (pin "1") (pinfunction "1_1") (pintype "passive"))
      (node (ref "R42") (pin "2") (pinfunction "2_2") (pintype "passive"))
      (node (ref "TPS1") (pin "C") (pinfunction "C_C") (pintype "passive"))
    )
    (net (code "59") (name "Net-(C4-Pad2)") (class "Default")
      (node (ref "C4") (pin "2") (pinfunction "2_2") (pintype "passive"))
      (node (ref "D6") (pin "A") (pinfunction "A_A") (pintype "passive"))
      (node (ref "D7") (pin "C") (pinfunction "C_C") (pintype "passive"))
    )
    (net (code "60") (name "Net-(C11-Pad1)") (class "Default")
      (node (ref "C11") (pin "1") (pinfunction "1_1") (pintype "passive"))
      (node (ref "D2") (pin "A") (pinfunction "A_A") (pintype "passive"))
      (node (ref "D3") (pin "C") (pinfunction "C_C") (pintype "passive"))
    )
    (net (code "61") (name "Net-(IC3-DIS)") (class "Default")
      (node (ref "IC3") (pin "7") (pinfunction "DIS_7") (pintype "input"))
      (node (ref "R16") (pin "1") (pinfunction "1_1") (pintype "passive"))
      (node (ref "R29") (pin "2") (pinfunction "2_2") (pintype "passive"))
    )
    (net (code "62") (name "Net-(IC3-TRE)") (class "Default")
      (node (ref "C24") (pin "+") (pinfunction "+_+") (pintype "passive"))
      (node (ref "IC3") (pin "2") (pinfunction "TRI_2") (pintype "input"))
      (node (ref "IC3") (pin "6") (pinfunction "TRE_6") (pintype "input"))
      (node (ref "R29") (pin "1") (pinfunction "1_1") (pintype "passive"))
    )
    (net (code "63") (name "Net-(IR2184SPBF1-VB)") (class "Default")
      (node (ref "C5") (pin "2") (pinfunction "2_2") (pintype "passive"))
      (node (ref "D12") (pin "C") (pinfunction "C_C") (pintype "passive"))
      (node (ref "D6") (pin "C") (pinfunction "C_C") (pintype "passive"))
      (node (ref "IR2184SPBF1") (pin "8") (pinfunction "VB_8") (pintype "bidirectional"))
    )
    (net (code "64") (name "Net-(IR2184SPBF2-VB)") (class "Default")
      (node (ref "C6") (pin "2") (pinfunction "2_2") (pintype "passive"))
      (node (ref "D2") (pin "C") (pinfunction "C_C") (pintype "passive"))
      (node (ref "D4") (pin "C") (pinfunction "C_C") (pintype "passive"))
      (node (ref "IR2184SPBF2") (pin "8") (pinfunction "VB_8") (pintype "bidirectional"))
    )
    (net (code "65") (name "Net-(JP1-Pad1)") (class "Default")
      (node (ref "JP1") (pin "1") (pinfunction "1_1") (pintype "passive"))
      (node (ref "R26") (pin "1") (pinfunction "1_1") (pintype "passive"))
    )
    (net (code "66") (name "Net-(JP3-Pad1)") (class "Default")
      (node (ref "JP3") (pin "1") (pinfunction "1_1") (pintype "passive"))
      (node (ref "R27") (pin "1") (pinfunction "1_1") (pintype "passive"))
    )
    (net (code "67") (name "Net-(LED1-PadC)") (class "Default")
      (node (ref "LED1") (pin "C") (pinfunction "C_C") (pintype "passive"))
      (node (ref "R1") (pin "2") (pinfunction "2_2") (pintype "passive"))
    )
    (net (code "68") (name "Net-(MA-KL)") (class "Default")
      (node (ref "C1") (pin "1") (pinfunction "1_1") (pintype "passive"))
      (node (ref "M") (pin "1") (pinfunction "KL_1") (pintype "passive"))
      (node (ref "Q1") (pin "3") (pinfunction "S_3") (pintype "passive"))
      (node (ref "Q2") (pin "4") (pinfunction "D_4") (pintype "passive"))
      (node (ref "R40") (pin "1") (pinfunction "1_1") (pintype "passive"))
      (node (ref "TPS2") (pin "C") (pinfunction "C_C") (pintype "passive"))
    )
    (net (code "69") (name "Net-(MB-KL)") (class "Default")
      (node (ref "C1") (pin "2") (pinfunction "2_2") (pintype "passive"))
      (node (ref "M") (pin "2") (pinfunction "KL_2") (pintype "passive"))
      (node (ref "Q3") (pin "3") (pinfunction "S_3") (pintype "passive"))
      (node (ref "Q4") (pin "4") (pinfunction "D_4") (pintype "passive"))
      (node (ref "R41") (pin "2") (pinfunction "2_2") (pintype "passive"))
      (node (ref "TPS3") (pin "C") (pinfunction "C_C") (pintype "passive"))
    )
    (net (code "70") (name "Net-(Q1-G)") (class "Default")
      (node (ref "D8") (pin "A") (pinfunction "A_A") (pintype "passive"))
      (node (ref "Q1") (pin "1") (pinfunction "G_1") (pintype "passive"))
      (node (ref "R4") (pin "1") (pinfunction "1_1") (pintype "passive"))
    )
    (net (code "71") (name "Net-(Q2-G)") (class "Default")
      (node (ref "D9") (pin "A") (pinfunction "A_A") (pintype "passive"))
      (node (ref "Q2") (pin "1") (pinfunction "G_1") (pintype "passive"))
      (node (ref "R5") (pin "1") (pinfunction "1_1") (pintype "passive"))
    )
    (net (code "72") (name "Net-(Q3-G)") (class "Default")
      (node (ref "D10") (pin "A") (pinfunction "A_A") (pintype "passive"))
      (node (ref "Q3") (pin "1") (pinfunction "G_1") (pintype "passive"))
      (node (ref "R7") (pin "2") (pinfunction "2_2") (pintype "passive"))
    )
    (net (code "73") (name "Net-(Q4-G)") (class "Default")
      (node (ref "D11") (pin "A") (pinfunction "A_A") (pintype "passive"))
      (node (ref "Q4") (pin "1") (pinfunction "G_1") (pintype "passive"))
      (node (ref "R6") (pin "2") (pinfunction "2_2") (pintype "passive"))
    )
    (net (code "74") (name "Net-(QP1-B)") (class "Default")
      (node (ref "QP1") (pin "1") (pinfunction "B_1") (pintype "passive"))
      (node (ref "R2") (pin "2") (pinfunction "2_2") (pintype "passive"))
      (node (ref "R8") (pin "2") (pinfunction "2_2") (pintype "passive"))
    )
    (net (code "75") (name "Net-(QP1-C)") (class "Default")
      (node (ref "QP1") (pin "3") (pinfunction "C_3") (pintype "passive"))
      (node (ref "R13") (pin "1") (pinfunction "1_1") (pintype "passive"))
      (node (ref "R31") (pin "2") (pinfunction "2_2") (pintype "passive"))
      (node (ref "R38") (pin "2") (pinfunction "2_2") (pintype "passive"))
    )
    (net (code "76") (name "Net-(QP2-B)") (class "Default")
      (node (ref "QP2") (pin "1") (pinfunction "B_1") (pintype "passive"))
      (node (ref "R35") (pin "1") (pinfunction "1_1") (pintype "passive"))
      (node (ref "R37") (pin "2") (pinfunction "2_2") (pintype "passive"))
    )
    (net (code "77") (name "Net-(QP2-C)") (class "Default")
      (node (ref "QP2") (pin "3") (pinfunction "C_3") (pintype "passive"))
      (node (ref "R17") (pin "1") (pinfunction "1_1") (pintype "passive"))
      (node (ref "R32") (pin "2") (pinfunction "2_2") (pintype "passive"))
    )
    (net (code "78") (name "Net-(QP3-B)") (class "Default")
      (node (ref "QP3") (pin "1") (pinfunction "B_1") (pintype "passive"))
      (node (ref "R36") (pin "2") (pinfunction "2_2") (pintype "passive"))
      (node (ref "R38") (pin "1") (pinfunction "1_1") (pintype "passive"))
    )
    (net (code "79") (name "Net-(QP3-C)") (class "Default")
      (node (ref "QP3") (pin "3") (pinfunction "C_3") (pintype "passive"))
      (node (ref "R42") (pin "1") (pinfunction "1_1") (pintype "passive"))
      (node (ref "R43") (pin "2") (pinfunction "2_2") (pintype "passive"))
    )
    (net (code "80") (name "Net-(QP4-B)") (class "Default")
      (node (ref "QP4") (pin "1") (pinfunction "B_1") (pintype "passive"))
      (node (ref "R31") (pin "1") (pinfunction "1_1") (pintype "passive"))
      (node (ref "R32") (pin "1") (pinfunction "1_1") (pintype "passive"))
    )
    (net (code "81") (name "Net-(QP4-C)") (class "Default")
      (node (ref "QP4") (pin "3") (pinfunction "C_3") (pintype "passive"))
      (node (ref "R33") (pin "2") (pinfunction "2_2") (pintype "passive"))
      (node (ref "R34") (pin "1") (pinfunction "1_1") (pintype "passive"))
    )
    (net (code "82") (name "unconnected-(COD_POD1D-S-Pad4)") (class "Default")
      (node (ref "COD_POD1") (pin "4") (pinfunction "S_4") (pintype "passive"))
    )
    (net (code "83") (name "unconnected-(COD_POD2D-S-Pad4)") (class "Default")
      (node (ref "COD_POD2") (pin "4") (pinfunction "S_4") (pintype "passive"))
    )
    (net (code "84") (name "unconnected-(COD_POD3D-S-Pad4)") (class "Default")
      (node (ref "COD_POD3") (pin "4") (pinfunction "S_4") (pintype "passive"))
    )
    (net (code "85") (name "unconnected-(EXT1-Pad11)") (class "Default")
      (node (ref "EXT1") (pin "11") (pinfunction "11_11") (pintype "passive"))
    )
    (net (code "86") (name "unconnected-(EXT1-Pad12)") (class "Default")
      (node (ref "EXT1") (pin "12") (pinfunction "12_12") (pintype "passive"))
    )
    (net (code "87") (name "unconnected-(EXT1-Pad15)") (class "Default")
      (node (ref "EXT1") (pin "15") (pinfunction "15_15") (pintype "passive"))
    )
    (net (code "88") (name "unconnected-(EXT1-Pad19)") (class "Default")
      (node (ref "EXT1") (pin "19") (pinfunction "19_19") (pintype "passive"))
    )
    (net (code "89") (name "unconnected-(EXT1-Pad20)") (class "Default")
      (node (ref "EXT1") (pin "20") (pinfunction "20_20") (pintype "passive"))
    )
    (net (code "90") (name "unconnected-(EXT2-Pad26)") (class "Default")
      (node (ref "EXT2") (pin "26") (pinfunction "26_26") (pintype "passive"))
    )
    (net (code "91") (name "unconnected-(IC3-CON-Pad5)") (class "Default")
      (node (ref "IC3") (pin "5") (pinfunction "CON_5") (pintype "input"))
    )
    (net (code "92") (name "unconnected-(IR2184SPBF1-SD{slash}-Pad2)") (class "Default")
      (node (ref "IR2184SPBF1") (pin "2") (pinfunction "SD/_2") (pintype "bidirectional"))
    )
    (net (code "93") (name "unconnected-(IR2184SPBF2-SD{slash}-Pad2)") (class "Default")
      (node (ref "IR2184SPBF2") (pin "2") (pinfunction "SD/_2") (pintype "bidirectional"))
    )
  )
)
